# pic6.net
KiCad netlist of a schematic drawn in EAGLE
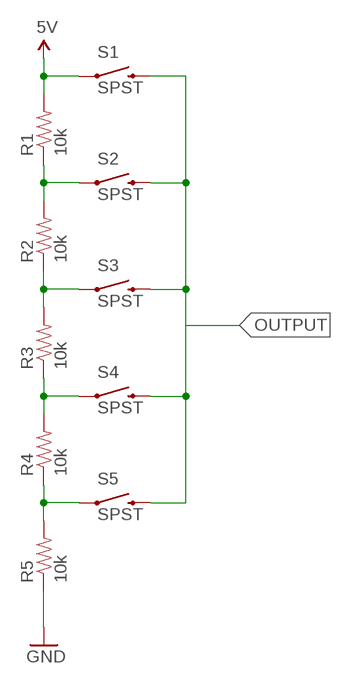
[diagram p0: schematic, sheet 1]

(export (version "E")
  (design (tool "Eeschema 10.0.6"))
  (components
    (comp (ref "R1")
      (value "10k")
      (footprint "eagle-import:0603-RES")
      (fields (field (name "PROD_ID") "RES-00818"))
      (libsource (lib "eagle-import") (part "330OHM1/10W1%(0603)"))
    )
    (comp (ref "R2")
      (value "10k")
      (footprint "eagle-import:0603-RES")
      (fields (field (name "PROD_ID") "RES-00818"))
      (libsource (lib "eagle-import") (part "330OHM1/10W1%(0603)"))
    )
    (comp (ref "R3")
      (value "10k")
      (footprint "eagle-import:0603-RES")
      (fields (field (name "PROD_ID") "RES-00818"))
      (libsource (lib "eagle-import") (part "330OHM1/10W1%(0603)"))
    )
    (comp (ref "R4")
      (value "10k")
      (footprint "eagle-import:0603-RES")
      (fields (field (name "PROD_ID") "RES-00818"))
      (libsource (lib "eagle-import") (part "330OHM1/10W1%(0603)"))
    )
    (comp (ref "R5")
      (value "10k")
      (footprint "eagle-import:0603-RES")
      (fields (field (name "PROD_ID") "RES-00818"))
      (libsource (lib "eagle-import") (part "330OHM1/10W1%(0603)"))
    )
    (comp (ref "S1")
      (value "SPST")
      (footprint "eagle-import:TACTILE-PTH-12MM")
      (libsource (lib "eagle-import") (part "SWITCH-MOMENTARY-212MM"))
    )
    (comp (ref "S2")
      (value "SPST")
      (footprint "eagle-import:TACTILE-PTH-12MM")
      (libsource (lib "eagle-import") (part "SWITCH-MOMENTARY-212MM"))
    )
    (comp (ref "S3")
      (value "SPST")
      (footprint "eagle-import:TACTILE-PTH-12MM")
      (libsource (lib "eagle-import") (part "SWITCH-MOMENTARY-212MM"))
    )
    (comp (ref "S4")
      (value "SPST")
      (footprint "eagle-import:TACTILE-PTH-12MM")
      (libsource (lib "eagle-import") (part "SWITCH-MOMENTARY-212MM"))
    )
    (comp (ref "S5")
      (value "SPST")
      (footprint "eagle-import:TACTILE-PTH-12MM")
      (libsource (lib "eagle-import") (part "SWITCH-MOMENTARY-212MM"))
    )
  )
  (nets
    (net (code "1") (name "5V") (class "Default")
      (node (ref "R1") (pin "2") (pinfunction "2_2") (pintype "passive"))
      (node (ref "S1") (pin "1") (pinfunction "1_1") (pintype "passive"))
    )
    (net (code "2") (name "GND") (class "Default")
      (node (ref "R5") (pin "1") (pinfunction "1_1") (pintype "passive"))
    )
    (net (code "3") (name "Net-(R1-Pad1)") (class "Default")
      (node (ref "R1") (pin "1") (pinfunction "1_1") (pintype "passive"))
      (node (ref "R2") (pin "2") (pinfunction "2_2") (pintype "passive"))
      (node (ref "S2") (pin "1") (pinfunction "1_1") (pintype "passive"))
    )
    (net (code "4") (name "Net-(R2-Pad1)") (class "Default")
      (node (ref "R2") (pin "1") (pinfunction "1_1") (pintype "passive"))
      (node (ref "R3") (pin "2") (pinfunction "2_2") (pintype "passive"))
      (node (ref "S3") (pin "1") (pinfunction "1_1") (pintype "passive"))
    )
    (net (code "5") (name "Net-(R3-Pad1)") (class "Default")
      (node (ref "R3") (pin "1") (pinfunction "1_1") (pintype "passive"))
      (node (ref "R4") (pin "2") (pinfunction "2_2") (pintype "passive"))
      (node (ref "S4") (pin "1") (pinfunction "1_1") (pintype "passive"))
    )
    (net (code "6") (name "Net-(R4-Pad1)") (class "Default")
      (node (ref "R4") (pin "1") (pinfunction "1_1") (pintype "passive"))
      (node (ref "R5") (pin "2") (pinfunction "2_2") (pintype "passive"))
      (node (ref "S5") (pin "1") (pinfunction "1_1") (pintype "passive"))
    )
    (net (code "7") (name "OUTPUT") (class "Default")
      (node (ref "S1") (pin "3") (pinfunction "2_3") (pintype "passive"))
      (node (ref "S2") (pin "3") (pinfunction "2_3") (pintype "passive"))
      (node (ref "S3") (pin "3") (pinfunction "2_3") (pintype "passive"))
      (node (ref "S4") (pin "3") (pinfunction "2_3") (pintype "passive"))
      (node (ref "S5") (pin "3") (pinfunction "2_3") (pintype "passive"))
    )
  )
)
